# Sheet1.net
KiCad netlist of a schematic drawn in Altium Designer
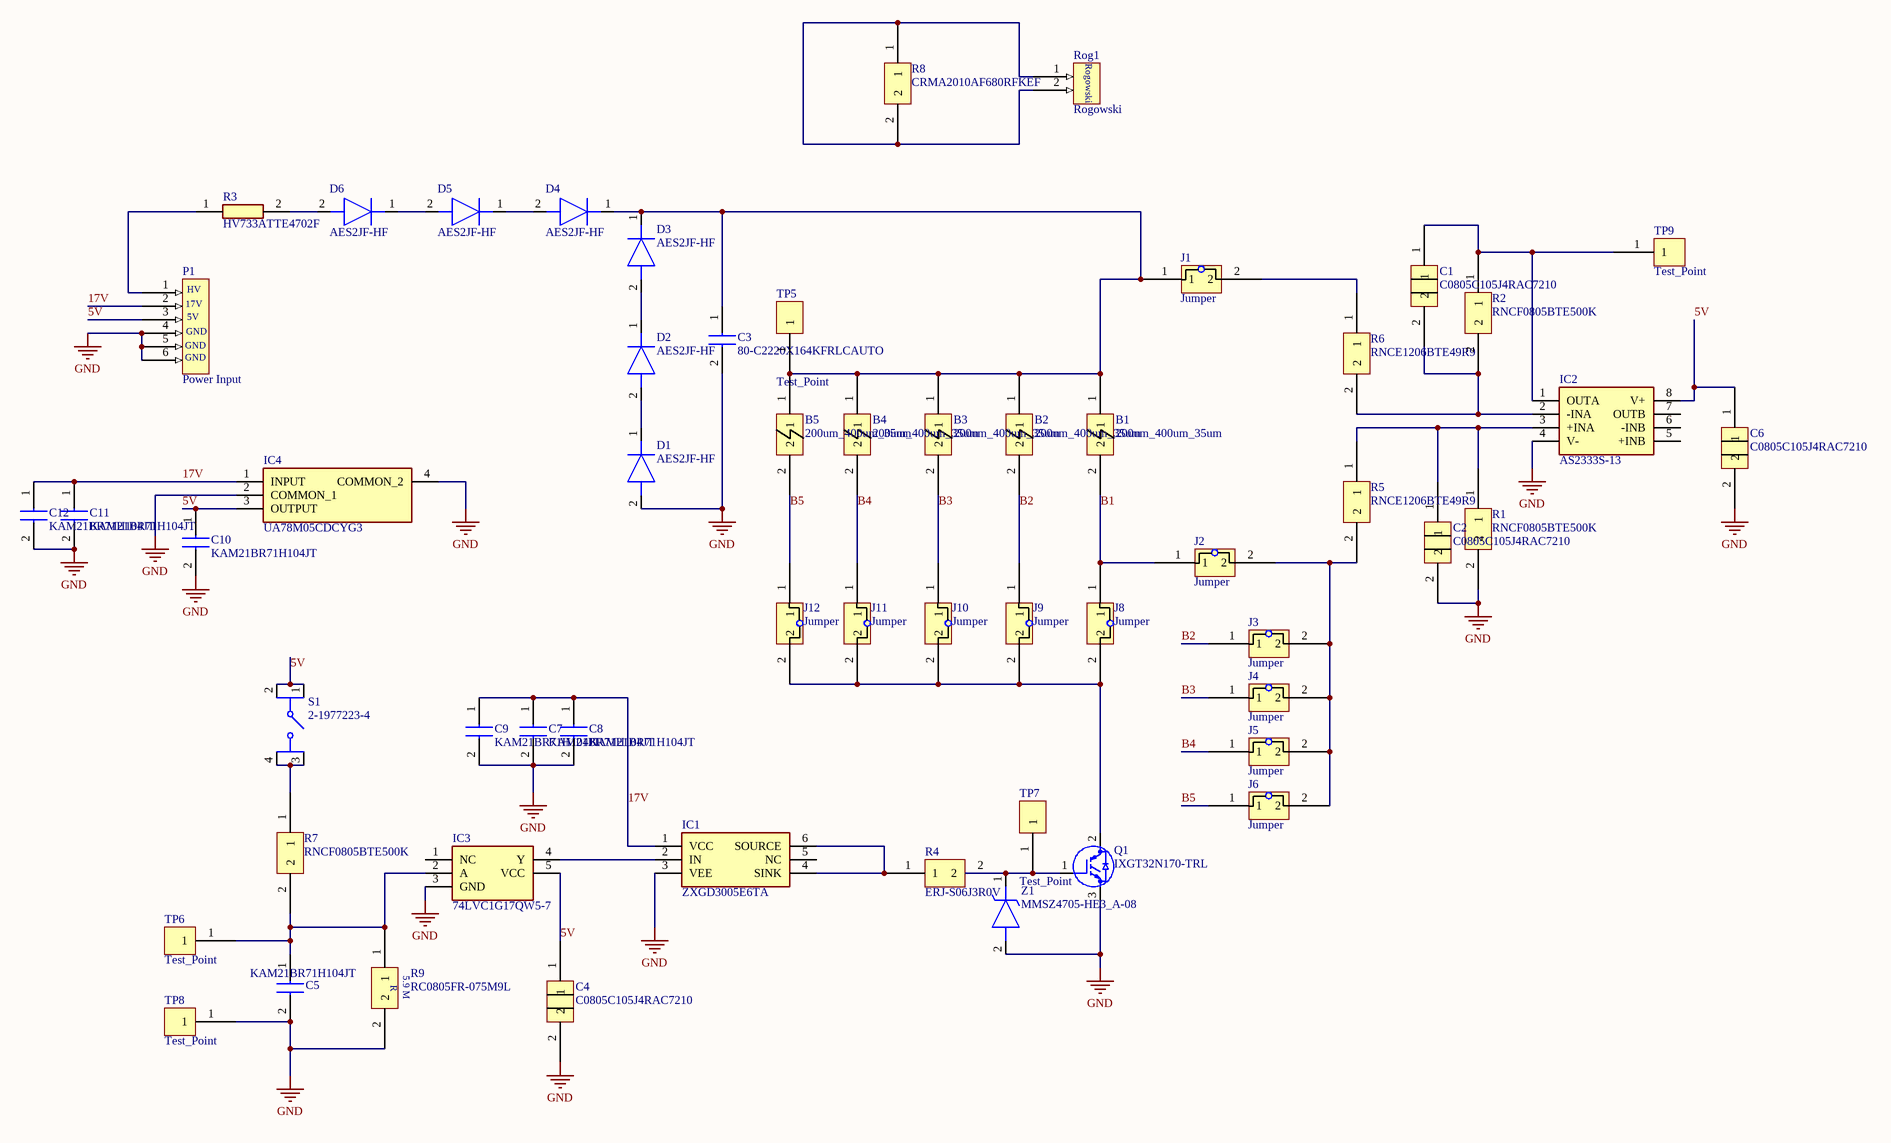
[diagram p0: Sheet1.SchDoc]

(export (version "E")
  (design (tool "Eeschema 10.0.6"))
  (components
    (comp (ref "B1")
      (value "200um_400um_35um")
      (footprint "Bridge_2")
      (libsource (lib "LEEFI_Lib") (part "Bridge_2"))
    )
    (comp (ref "B2")
      (value "200um_400um_35um")
      (footprint "Bridge_2")
      (libsource (lib "LEEFI_Lib") (part "Bridge_2"))
    )
    (comp (ref "B3")
      (value "200um_400um_35um")
      (footprint "Bridge_2")
      (libsource (lib "LEEFI_Lib") (part "Bridge_2"))
    )
    (comp (ref "B4")
      (value "200um_400um_35um")
      (footprint "Bridge_2")
      (libsource (lib "LEEFI_Lib") (part "Bridge_2"))
    )
    (comp (ref "B5")
      (value "200um_400um_35um")
      (footprint "Bridge_2")
      (libsource (lib "LEEFI_Lib") (part "Bridge_2"))
    )
    (comp (ref "C1")
      (value "C0805C105J4RAC7210")
      (footprint "RESC2012X60N")
      (description "0805 Ceramic")
      (libsource (lib "LEEFI_Lib") (part "1u 10V"))
    )
    (comp (ref "C2")
      (value "C0805C105J4RAC7210")
      (footprint "RESC2012X60N")
      (description "0805 Ceramic")
      (libsource (lib "LEEFI_Lib") (part "1u 10V"))
    )
    (comp (ref "C3")
      (value "80-C2220X164KFRLCAUTO")
      (footprint "CAPC5750X280N")
      (description "0.16uF\r\n1500V")
      (libsource (lib "LEEFI_Lib") (part "80-C2220X164KFRLCAUTO"))
    )
    (comp (ref "C4")
      (value "C0805C105J4RAC7210")
      (footprint "RESC2012X60N")
      (description "0805 Ceramic")
      (libsource (lib "LEEFI_Lib") (part "1u 10V"))
    )
    (comp (ref "C5")
      (value "KAM21BR71H104JT")
      (footprint "SamacSys:CAPC2012X94N")
      (description "Capacitor")
      (fields (field (name "MOUSER PART NUMBER") "581-KAM21BR71H104JT"))
      (libsource (lib "*") (part "KAM21BR71H104JT"))
    )
    (comp (ref "C6")
      (value "C0805C105J4RAC7210")
      (footprint "RESC2012X60N")
      (description "0805 Ceramic")
      (libsource (lib "LEEFI_Lib") (part "1u 10V"))
    )
    (comp (ref "C7")
      (value "KAM21BR71H104JT")
      (footprint "SamacSys:CAPC2012X94N")
      (description "Capacitor")
      (fields (field (name "MOUSER PART NUMBER") "581-KAM21BR71H104JT"))
      (libsource (lib "*") (part "KAM21BR71H104JT"))
    )
    (comp (ref "C8")
      (value "KAM21BR71H104JT")
      (footprint "SamacSys:CAPC2012X94N")
      (description "Capacitor")
      (fields (field (name "MOUSER PART NUMBER") "581-KAM21BR71H104JT"))
      (libsource (lib "*") (part "KAM21BR71H104JT"))
    )
    (comp (ref "C9")
      (value "KAM21BR71H104JT")
      (footprint "SamacSys:CAPC2012X94N")
      (description "Capacitor")
      (fields (field (name "MOUSER PART NUMBER") "581-KAM21BR71H104JT"))
      (libsource (lib "*") (part "KAM21BR71H104JT"))
    )
    (comp (ref "C10")
      (value "KAM21BR71H104JT")
      (footprint "SamacSys:CAPC2012X94N")
      (description "Capacitor")
      (fields (field (name "MOUSER PART NUMBER") "581-KAM21BR71H104JT"))
      (libsource (lib "*") (part "KAM21BR71H104JT"))
    )
    (comp (ref "C11")
      (value "KAM21BR71H104JT")
      (footprint "SamacSys:CAPC2012X94N")
      (description "Capacitor")
      (fields (field (name "MOUSER PART NUMBER") "581-KAM21BR71H104JT"))
      (libsource (lib "*") (part "KAM21BR71H104JT"))
    )
    (comp (ref "C12")
      (value "KAM21BR71H104JT")
      (footprint "SamacSys:CAPC2012X94N")
      (description "Capacitor")
      (fields (field (name "MOUSER PART NUMBER") "581-KAM21BR71H104JT"))
      (libsource (lib "*") (part "KAM21BR71H104JT"))
    )
    (comp (ref "D1")
      (value "AES2JF-HF")
      (footprint "SamacSys:SODFL5226X110N")
      (description "Diode")
      (fields (field (name "MOUSER PART NUMBER") "750-AES2JF-HF"))
      (libsource (lib "*") (part "AES2JF-HF"))
    )
    (comp (ref "D2")
      (value "AES2JF-HF")
      (footprint "SamacSys:SODFL5226X110N")
      (description "Diode")
      (fields (field (name "MOUSER PART NUMBER") "750-AES2JF-HF"))
      (libsource (lib "*") (part "AES2JF-HF"))
    )
    (comp (ref "D3")
      (value "AES2JF-HF")
      (footprint "SamacSys:SODFL5226X110N")
      (description "Diode")
      (fields (field (name "MOUSER PART NUMBER") "750-AES2JF-HF"))
      (libsource (lib "*") (part "AES2JF-HF"))
    )
    (comp (ref "D4")
      (value "AES2JF-HF")
      (footprint "SamacSys:SODFL5226X110N")
      (description "Diode")
      (fields (field (name "MOUSER PART NUMBER") "750-AES2JF-HF"))
      (libsource (lib "*") (part "AES2JF-HF"))
    )
    (comp (ref "D5")
      (value "AES2JF-HF")
      (footprint "SamacSys:SODFL5226X110N")
      (description "Diode")
      (fields (field (name "MOUSER PART NUMBER") "750-AES2JF-HF"))
      (libsource (lib "*") (part "AES2JF-HF"))
    )
    (comp (ref "D6")
      (value "AES2JF-HF")
      (footprint "SamacSys:SODFL5226X110N")
      (description "Diode")
      (fields (field (name "MOUSER PART NUMBER") "750-AES2JF-HF"))
      (libsource (lib "*") (part "AES2JF-HF"))
    )
    (comp (ref "IC1")
      (value "ZXGD3005E6TA")
      (footprint "SamacSys:SOT95P285X140-6N")
      (description "Integrated Circuit")
      (fields (field (name "MOUSER PART NUMBER") "522-ZXGD3005E6TA"))
      (libsource (lib "*") (part "ZXGD3005E6TA"))
    )
    (comp (ref "IC2")
      (value "AS2333S-13")
      (footprint "SamacSys:SOIC127P600X150-8N")
      (description "Integrated Circuit")
      (fields (field (name "MOUSER PART NUMBER") "621-AS2333S-13"))
      (libsource (lib "*") (part "AS2333S-13"))
    )
    (comp (ref "IC3")
      (value "74LVC1G17QW5-7")
      (footprint "SamacSys:SOT95P285X140-5N")
      (description "Integrated Circuit")
      (fields (field (name "MOUSER PART NUMBER") "621-74LVC1G17QW5-7"))
      (libsource (lib "*") (part "74LVC1G17QW5-7"))
    )
    (comp (ref "IC4")
      (value "UA78M05CDCYG3")
      (footprint "SamacSys:SOT230P700X180-4N")
      (description "Integrated Circuit")
      (fields (field (name "MOUSER PART NUMBER") "595-UA78M05CDCYG3"))
      (libsource (lib "*") (part "UA78M05CDCYG3"))
    )
    (comp (ref "J1") (value "Jumper") (footprint "Jumper") (libsource (lib "LEEFI_Lib") (part "Jumper")))
    (comp (ref "J2") (value "Jumper") (footprint "Jumper") (libsource (lib "LEEFI_Lib") (part "Jumper")))
    (comp (ref "J3") (value "Jumper") (footprint "Jumper") (libsource (lib "LEEFI_Lib") (part "Jumper")))
    (comp (ref "J4") (value "Jumper") (footprint "Jumper") (libsource (lib "LEEFI_Lib") (part "Jumper")))
    (comp (ref "J5") (value "Jumper") (footprint "Jumper") (libsource (lib "LEEFI_Lib") (part "Jumper")))
    (comp (ref "J6") (value "Jumper") (footprint "Jumper") (libsource (lib "LEEFI_Lib") (part "Jumper")))
    (comp (ref "J8") (value "Jumper") (footprint "Jumper") (libsource (lib "") (part "Jumper_1")))
    (comp (ref "J9") (value "Jumper") (footprint "Jumper") (libsource (lib "") (part "Jumper_1")))
    (comp (ref "J10") (value "Jumper") (footprint "Jumper") (libsource (lib "") (part "Jumper_1")))
    (comp (ref "J11") (value "Jumper") (footprint "Jumper") (libsource (lib "") (part "Jumper_1")))
    (comp (ref "J12") (value "Jumper") (footprint "Jumper") (libsource (lib "") (part "Jumper_1")))
    (comp (ref "P1")
      (value "Power Input")
      (footprint "Power Input")
      (libsource (lib "LEEFI_Lib") (part "Power Input"))
    )
    (comp (ref "Q1")
      (value "IXGT32N170-TRL")
      (footprint "SamacSys:IXGT32N170TRL")
      (description "Transistor IGBT")
      (fields (field (name "MOUSER PART NUMBER") "747-IXGT32N170-TRL"))
      (libsource (lib "*") (part "IXGT32N170-TRL"))
    )
    (comp (ref "R1")
      (value "RNCF0805BTE500K")
      (footprint "RESC2012X60N")
      (libsource (lib "LEEFI_Lib") (part "500k 0.1%"))
    )
    (comp (ref "R2")
      (value "RNCF0805BTE500K")
      (footprint "RESC2012X60N")
      (libsource (lib "LEEFI_Lib") (part "500k 0.1%"))
    )
    (comp (ref "R3")
      (value "HV733ATTE4702F")
      (footprint "SamacSys:RESC6331X70N")
      (description "47k 3kV 1W")
      (libsource (lib "*") (part "HV733ATTE4702F"))
    )
    (comp (ref "R4")
      (value "ERJ-S06J3R0V")
      (footprint "RESC2012X60N")
      (description "3 Ohm 125mW 0805 (2012)")
      (libsource (lib "LEEFI_Lib") (part "3 Ohm Res"))
    )
    (comp (ref "R5")
      (value "RNCE1206BTE49R9")
      (footprint "RESC3216X60N")
      (libsource (lib "LEEFI_Lib") (part "49.9 Ohm 0.1%"))
    )
    (comp (ref "R6")
      (value "RNCE1206BTE49R9")
      (footprint "RESC3216X60N")
      (libsource (lib "LEEFI_Lib") (part "49.9 Ohm 0.1%"))
    )
    (comp (ref "R7")
      (value "RNCF0805BTE500K")
      (footprint "RESC2012X60N")
      (libsource (lib "LEEFI_Lib") (part "500k 0.1%"))
    )
    (comp (ref "R8")
      (value "CRMA2010AF680RFKEF")
      (footprint "RESC3216X65N")
      (description "500mW 1%")
      (libsource (lib "LEEFI_Lib") (part "680 Ohm 2kV"))
    )
    (comp (ref "R9")
      (value "RC0805FR-075M9L")
      (footprint "RESC2012X60N")
      (description "1% 1/8W")
      (libsource (lib "LEEFI_Lib") (part "5.9MOhm Res"))
    )
    (comp (ref "Rog1")
      (value "Rogowski")
      (footprint "Rogowski")
      (libsource (lib "LEEFI_Lib") (part "Rogowski"))
    )
    (comp (ref "S1")
      (value "2-1977223-4")
      (footprint "SamacSys:219772234")
      (description "Switch (4-Pin Push)")
      (fields (field (name "MOUSER PART NUMBER") "506-2-1977223-4"))
      (libsource (lib "*") (part "2-1977223-4"))
    )
    (comp (ref "TP5")
      (value "Test_Point")
      (footprint "TestPoint")
      (libsource (lib "LEEFI_Lib") (part "Test_Point"))
    )
    (comp (ref "TP6") (value "Test_Point") (footprint "TestPoint") (libsource (lib "") (part "Test_Point_1")))
    (comp (ref "TP7")
      (value "Test_Point")
      (footprint "TestPoint")
      (libsource (lib "LEEFI_Lib") (part "Test_Point"))
    )
    (comp (ref "TP8") (value "Test_Point") (footprint "TestPoint") (libsource (lib "") (part "Test_Point_1")))
    (comp (ref "TP9") (value "Test_Point") (footprint "TestPoint") (libsource (lib "") (part "Test_Point_2")))
    (comp (ref "Z1")
      (value "MMSZ4705-HE3_A-08")
      (footprint "SamacSys:SOD3716X135N")
      (description "18V Zener Diode")
      (fields (field (name "MOUSER PART NUMBER") "78-MMSZ4705-HE3_A-08"))
      (libsource (lib "*") (part "MMSZ4705-HE3_A-08"))
    )
  )
  (nets
    (net (code "1") (name "/5V") (class "Default")
      (node (ref "C10") (pin "1") (pinfunction "1_1") (pintype "passive"))
      (node (ref "C4") (pin "1") (pinfunction "1_1") (pintype "passive"))
      (node (ref "C6") (pin "1") (pinfunction "1_1") (pintype "passive"))
      (node (ref "IC2") (pin "8") (pinfunction "V+_8") (pintype "passive"))
      (node (ref "IC3") (pin "5") (pinfunction "VCC_5") (pintype "passive"))
      (node (ref "IC4") (pin "3") (pinfunction "OUTPUT_3") (pintype "passive"))
      (node (ref "P1") (pin "3") (pintype "input"))
      (node (ref "S1") (pin "1") (pinfunction "COM_1_1") (pintype "passive"))
      (node (ref "S1") (pin "2") (pinfunction "COM_2_2") (pintype "passive"))
    )
    (net (code "2") (name "/17V") (class "Default")
      (node (ref "C11") (pin "1") (pinfunction "1_1") (pintype "passive"))
      (node (ref "C12") (pin "1") (pinfunction "1_1") (pintype "passive"))
      (node (ref "C7") (pin "1") (pinfunction "1_1") (pintype "passive"))
      (node (ref "C8") (pin "1") (pinfunction "1_1") (pintype "passive"))
      (node (ref "C9") (pin "1") (pinfunction "1_1") (pintype "passive"))
      (node (ref "IC1") (pin "1") (pinfunction "VCC_1") (pintype "passive"))
      (node (ref "IC4") (pin "1") (pinfunction "INPUT_1") (pintype "passive"))
      (node (ref "P1") (pin "2") (pintype "input"))
    )
    (net (code "3") (name "/B1") (class "Default")
      (node (ref "B1") (pin "2") (pinfunction "2_2") (pintype "passive"))
      (node (ref "J2") (pin "1") (pinfunction "1_1") (pintype "passive"))
      (node (ref "J8") (pin "1") (pinfunction "1_1") (pintype "passive"))
    )
    (net (code "4") (name "/B2") (class "Default")
      (node (ref "B2") (pin "2") (pinfunction "2_2") (pintype "passive"))
      (node (ref "J3") (pin "1") (pinfunction "1_1") (pintype "passive"))
      (node (ref "J9") (pin "1") (pinfunction "1_1") (pintype "passive"))
    )
    (net (code "5") (name "/B3") (class "Default")
      (node (ref "B3") (pin "2") (pinfunction "2_2") (pintype "passive"))
      (node (ref "J10") (pin "1") (pinfunction "1_1") (pintype "passive"))
      (node (ref "J4") (pin "1") (pinfunction "1_1") (pintype "passive"))
    )
    (net (code "6") (name "/B4") (class "Default")
      (node (ref "B4") (pin "2") (pinfunction "2_2") (pintype "passive"))
      (node (ref "J11") (pin "1") (pinfunction "1_1") (pintype "passive"))
      (node (ref "J5") (pin "1") (pinfunction "1_1") (pintype "passive"))
    )
    (net (code "7") (name "/B5") (class "Default")
      (node (ref "B5") (pin "2") (pinfunction "2_2") (pintype "passive"))
      (node (ref "J12") (pin "1") (pinfunction "1_1") (pintype "passive"))
      (node (ref "J6") (pin "1") (pinfunction "1_1") (pintype "passive"))
    )
    (net (code "8") (name "GND") (class "Default")
      (node (ref "C10") (pin "2") (pinfunction "2_2") (pintype "passive"))
      (node (ref "C11") (pin "2") (pinfunction "2_2") (pintype "passive"))
      (node (ref "C12") (pin "2") (pinfunction "2_2") (pintype "passive"))
      (node (ref "C2") (pin "2") (pinfunction "2_2") (pintype "passive"))
      (node (ref "C3") (pin "2") (pinfunction "2_2") (pintype "passive"))
      (node (ref "C4") (pin "2") (pinfunction "2_2") (pintype "passive"))
      (node (ref "C5") (pin "2") (pinfunction "2_2") (pintype "passive"))
      (node (ref "C6") (pin "2") (pinfunction "2_2") (pintype "passive"))
      (node (ref "C7") (pin "2") (pinfunction "2_2") (pintype "passive"))
      (node (ref "C8") (pin "2") (pinfunction "2_2") (pintype "passive"))
      (node (ref "C9") (pin "2") (pinfunction "2_2") (pintype "passive"))
      (node (ref "D1") (pin "2") (pinfunction "A_2") (pintype "passive"))
      (node (ref "IC1") (pin "3") (pinfunction "VEE_3") (pintype "passive"))
      (node (ref "IC2") (pin "4") (pinfunction "V-_4") (pintype "passive"))
      (node (ref "IC3") (pin "3") (pinfunction "GND_3") (pintype "passive"))
      (node (ref "IC4") (pin "2") (pinfunction "COMMON_1_2") (pintype "passive"))
      (node (ref "IC4") (pin "4") (pinfunction "COMMON_2_4") (pintype "passive"))
      (node (ref "P1") (pin "4") (pintype "input"))
      (node (ref "P1") (pin "5") (pintype "input"))
      (node (ref "P1") (pin "6") (pintype "input"))
      (node (ref "Q1") (pin "3") (pinfunction "E_3") (pintype "passive"))
      (node (ref "R1") (pin "2") (pinfunction "2_2") (pintype "passive"))
      (node (ref "R9") (pin "2") (pinfunction "2_2") (pintype "passive"))
      (node (ref "TP8") (pin "1") (pinfunction "1_1") (pintype "passive"))
      (node (ref "Z1") (pin "2") (pinfunction "A_2") (pintype "passive"))
    )
    (net (code "9") (name "Net-(D1-K)") (class "Default")
      (node (ref "D1") (pin "1") (pinfunction "K_1") (pintype "passive"))
      (node (ref "D2") (pin "2") (pinfunction "A_2") (pintype "passive"))
    )
    (net (code "10") (name "Net-(D2-K)") (class "Default")
      (node (ref "D2") (pin "1") (pinfunction "K_1") (pintype "passive"))
      (node (ref "D3") (pin "2") (pinfunction "A_2") (pintype "passive"))
    )
    (net (code "11") (name "Net-(D3-K)") (class "Default")
      (node (ref "B1") (pin "1") (pinfunction "1_1") (pintype "passive"))
      (node (ref "B2") (pin "1") (pinfunction "1_1") (pintype "passive"))
      (node (ref "B3") (pin "1") (pinfunction "1_1") (pintype "passive"))
      (node (ref "B4") (pin "1") (pinfunction "1_1") (pintype "passive"))
      (node (ref "B5") (pin "1") (pinfunction "1_1") (pintype "passive"))
      (node (ref "C3") (pin "1") (pinfunction "1_1") (pintype "passive"))
      (node (ref "D3") (pin "1") (pinfunction "K_1") (pintype "passive"))
      (node (ref "D4") (pin "1") (pinfunction "K_1") (pintype "passive"))
      (node (ref "J1") (pin "1") (pinfunction "1_1") (pintype "passive"))
      (node (ref "TP5") (pin "1") (pinfunction "1_1") (pintype "passive"))
    )
    (net (code "12") (name "Net-(D4-A)") (class "Default")
      (node (ref "D4") (pin "2") (pinfunction "A_2") (pintype "passive"))
      (node (ref "D5") (pin "1") (pinfunction "K_1") (pintype "passive"))
    )
    (net (code "13") (name "Net-(D5-A)") (class "Default")
      (node (ref "D5") (pin "2") (pinfunction "A_2") (pintype "passive"))
      (node (ref "D6") (pin "1") (pinfunction "K_1") (pintype "passive"))
    )
    (net (code "14") (name "Net-(D6-A)") (class "Default")
      (node (ref "D6") (pin "2") (pinfunction "A_2") (pintype "passive"))
      (node (ref "R3") (pin "2") (pinfunction "2_2") (pintype "passive"))
    )
    (net (code "15") (name "Net-(IC1-IN)") (class "Default")
      (node (ref "IC1") (pin "2") (pinfunction "IN_2") (pintype "passive"))
      (node (ref "IC3") (pin "4") (pinfunction "Y_4") (pintype "passive"))
    )
    (net (code "16") (name "Net-(IC1-SINK)") (class "Default")
      (node (ref "IC1") (pin "4") (pinfunction "SINK_4") (pintype "passive"))
      (node (ref "IC1") (pin "6") (pinfunction "SOURCE_6") (pintype "passive"))
      (node (ref "R4") (pin "1") (pinfunction "1_1") (pintype "passive"))
    )
    (net (code "17") (name "Net-(IC2-+INA)") (class "Default")
      (node (ref "C2") (pin "1") (pinfunction "1_1") (pintype "passive"))
      (node (ref "IC2") (pin "3") (pinfunction "+INA_3") (pintype "passive"))
      (node (ref "R1") (pin "1") (pinfunction "1_1") (pintype "passive"))
      (node (ref "R5") (pin "1") (pinfunction "1_1") (pintype "passive"))
    )
    (net (code "18") (name "Net-(IC2--INA)") (class "Default")
      (node (ref "C1") (pin "2") (pinfunction "2_2") (pintype "passive"))
      (node (ref "IC2") (pin "2") (pinfunction "-INA_2") (pintype "passive"))
      (node (ref "R2") (pin "2") (pinfunction "2_2") (pintype "passive"))
      (node (ref "R6") (pin "2") (pinfunction "2_2") (pintype "passive"))
    )
    (net (code "19") (name "Net-(IC2-OUTA)") (class "Default")
      (node (ref "C1") (pin "1") (pinfunction "1_1") (pintype "passive"))
      (node (ref "IC2") (pin "1") (pinfunction "OUTA_1") (pintype "passive"))
      (node (ref "R2") (pin "1") (pinfunction "1_1") (pintype "passive"))
      (node (ref "TP9") (pin "1") (pinfunction "1_1") (pintype "passive"))
    )
    (net (code "20") (name "Net-(IC3-A)") (class "Default")
      (node (ref "C5") (pin "1") (pinfunction "1_1") (pintype "passive"))
      (node (ref "IC3") (pin "2") (pinfunction "A_2") (pintype "passive"))
      (node (ref "R7") (pin "2") (pinfunction "2_2") (pintype "passive"))
      (node (ref "R9") (pin "1") (pinfunction "1_1") (pintype "passive"))
      (node (ref "TP6") (pin "1") (pinfunction "1_1") (pintype "passive"))
    )
    (net (code "21") (name "Net-(J1-Pad2)") (class "Default")
      (node (ref "J1") (pin "2") (pinfunction "2_2") (pintype "passive"))
      (node (ref "R6") (pin "1") (pinfunction "1_1") (pintype "passive"))
    )
    (net (code "22") (name "Net-(J2-Pad2)") (class "Default")
      (node (ref "J2") (pin "2") (pinfunction "2_2") (pintype "passive"))
      (node (ref "J3") (pin "2") (pinfunction "2_2") (pintype "passive"))
      (node (ref "J4") (pin "2") (pinfunction "2_2") (pintype "passive"))
      (node (ref "J5") (pin "2") (pinfunction "2_2") (pintype "passive"))
      (node (ref "J6") (pin "2") (pinfunction "2_2") (pintype "passive"))
      (node (ref "R5") (pin "2") (pinfunction "2_2") (pintype "passive"))
    )
    (net (code "23") (name "Net-(P1-Pad1)") (class "Default")
      (node (ref "P1") (pin "1") (pintype "input"))
      (node (ref "R3") (pin "1") (pinfunction "1_1") (pintype "passive"))
    )
    (net (code "24") (name "Net-(Q1-C)") (class "Default")
      (node (ref "J10") (pin "2") (pinfunction "2_2") (pintype "passive"))
      (node (ref "J11") (pin "2") (pinfunction "2_2") (pintype "passive"))
      (node (ref "J12") (pin "2") (pinfunction "2_2") (pintype "passive"))
      (node (ref "J8") (pin "2") (pinfunction "2_2") (pintype "passive"))
      (node (ref "J9") (pin "2") (pinfunction "2_2") (pintype "passive"))
      (node (ref "Q1") (pin "2") (pinfunction "C_2") (pintype "passive"))
    )
    (net (code "25") (name "Net-(Q1-G)") (class "Default")
      (node (ref "Q1") (pin "1") (pinfunction "G_1") (pintype "passive"))
      (node (ref "R4") (pin "2") (pinfunction "2_2") (pintype "passive"))
      (node (ref "TP7") (pin "1") (pinfunction "1_1") (pintype "passive"))
      (node (ref "Z1") (pin "1") (pinfunction "K_1") (pintype "passive"))
    )
    (net (code "26") (name "Net-(R8-Pad1)") (class "Default")
      (node (ref "R8") (pin "1") (pinfunction "1_1") (pintype "passive"))
      (node (ref "R8") (pin "2") (pinfunction "2_2") (pintype "passive"))
      (node (ref "Rog1") (pin "1") (pintype "input"))
      (node (ref "Rog1") (pin "2") (pintype "input"))
    )
    (net (code "27") (name "Net-(S1-NO_1)") (class "Default")
      (node (ref "R7") (pin "1") (pinfunction "1_1") (pintype "passive"))
      (node (ref "S1") (pin "3") (pinfunction "NO_1_3") (pintype "passive"))
      (node (ref "S1") (pin "4") (pinfunction "NO_2_4") (pintype "passive"))
    )
    (net (code "28") (name "unconnected-(IC1-NC-Pad5)") (class "Default")
      (node (ref "IC1") (pin "5") (pinfunction "NC_5") (pintype "passive"))
    )
    (net (code "29") (name "unconnected-(IC2-+INB-Pad5)") (class "Default")
      (node (ref "IC2") (pin "5") (pinfunction "+INB_5") (pintype "passive"))
    )
    (net (code "30") (name "unconnected-(IC2--INB-Pad6)") (class "Default")
      (node (ref "IC2") (pin "6") (pinfunction "-INB_6") (pintype "passive"))
    )
    (net (code "31") (name "unconnected-(IC2-OUTB-Pad7)") (class "Default")
      (node (ref "IC2") (pin "7") (pinfunction "OUTB_7") (pintype "passive"))
    )
    (net (code "32") (name "unconnected-(IC3-NC-Pad1)") (class "Default")
      (node (ref "IC3") (pin "1") (pinfunction "NC_1") (pintype "passive"))
    )
  )
)
